# BLDC.net
KiCad netlist of a schematic drawn in EAGLE
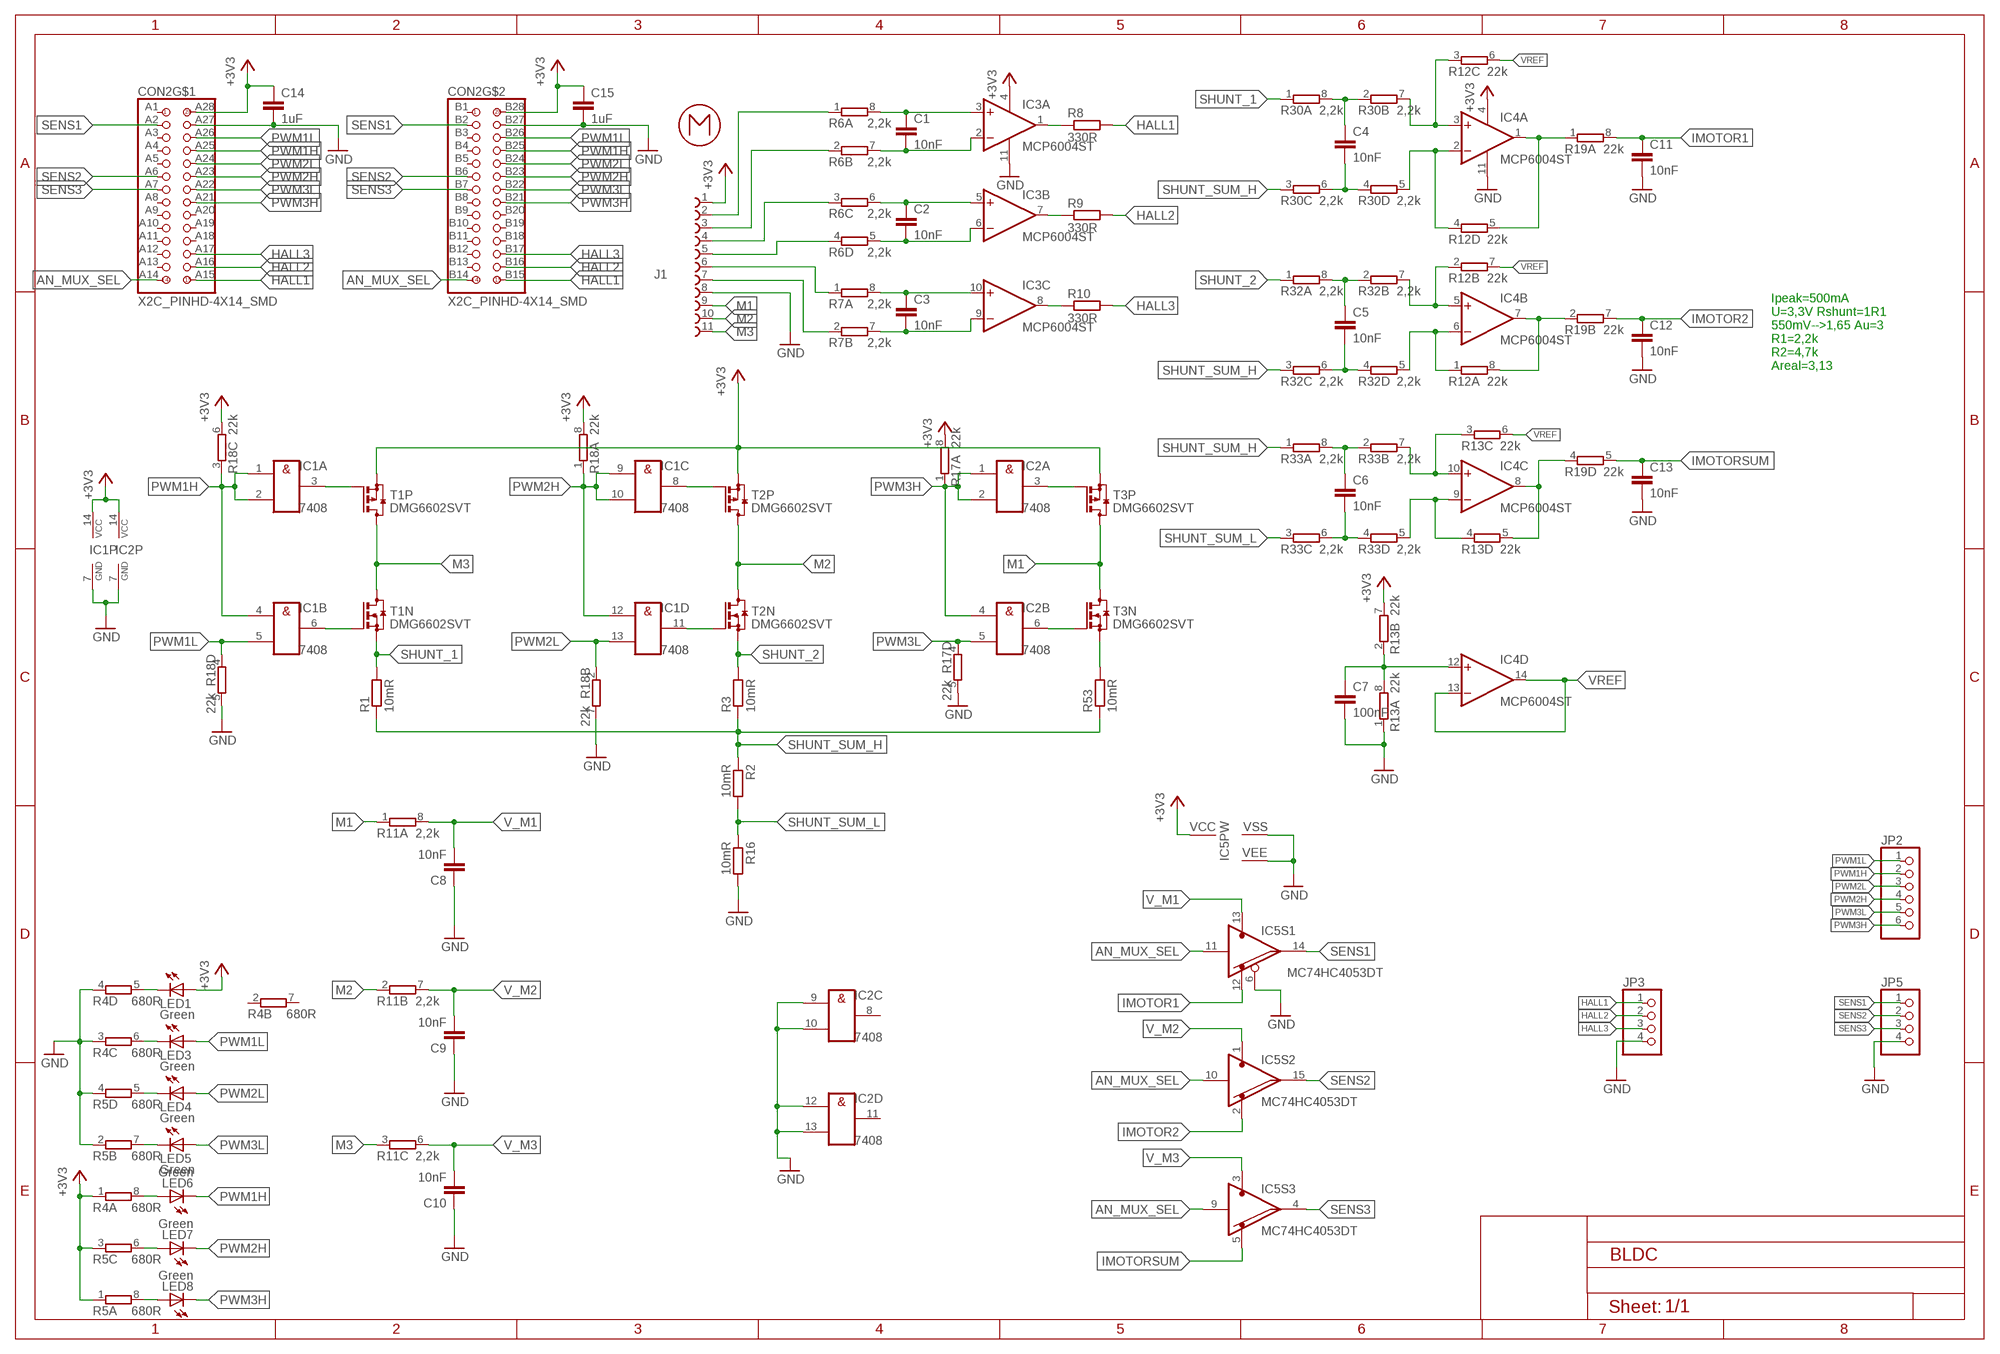
[diagram p0: schematic, sheet 1]

(export (version "E")
  (design (tool "Eeschema 10.0.6"))
  (components
    (comp (ref "C1")
      (value "10nF")
      (footprint "eagle-import:C0603K")
      (libsource (lib "eagle-import") (part "C-EU-SMD_0603_10NF"))
    )
    (comp (ref "C2")
      (value "10nF")
      (footprint "eagle-import:C0603K")
      (libsource (lib "eagle-import") (part "C-EU-SMD_0603_10NF"))
    )
    (comp (ref "C3")
      (value "10nF")
      (footprint "eagle-import:C0603K")
      (libsource (lib "eagle-import") (part "C-EU-SMD_0603_10NF"))
    )
    (comp (ref "C4")
      (value "10nF")
      (footprint "eagle-import:C0603K")
      (libsource (lib "eagle-import") (part "C-EU-SMD_0603_10NF"))
    )
    (comp (ref "C5")
      (value "10nF")
      (footprint "eagle-import:C0603K")
      (libsource (lib "eagle-import") (part "C-EU-SMD_0603_10NF"))
    )
    (comp (ref "C6")
      (value "10nF")
      (footprint "eagle-import:C0603K")
      (libsource (lib "eagle-import") (part "C-EU-SMD_0603_10NF"))
    )
    (comp (ref "C7")
      (value "100nF")
      (footprint "eagle-import:C0603K")
      (libsource (lib "eagle-import") (part "C-EU-SMD_0603_100NF_50V"))
    )
    (comp (ref "C8")
      (value "10nF")
      (footprint "eagle-import:C0603K")
      (libsource (lib "eagle-import") (part "C-EU-SMD_0603_10NF"))
    )
    (comp (ref "C9")
      (value "10nF")
      (footprint "eagle-import:C0603K")
      (libsource (lib "eagle-import") (part "C-EU-SMD_0603_10NF"))
    )
    (comp (ref "C10")
      (value "10nF")
      (footprint "eagle-import:C0603K")
      (libsource (lib "eagle-import") (part "C-EU-SMD_0603_10NF"))
    )
    (comp (ref "C11")
      (value "10nF")
      (footprint "eagle-import:C0603K")
      (libsource (lib "eagle-import") (part "C-EU-SMD_0603_10NF"))
    )
    (comp (ref "C12")
      (value "10nF")
      (footprint "eagle-import:C0603K")
      (libsource (lib "eagle-import") (part "C-EU-SMD_0603_10NF"))
    )
    (comp (ref "C13")
      (value "10nF")
      (footprint "eagle-import:C0603K")
      (libsource (lib "eagle-import") (part "C-EU-SMD_0603_10NF"))
    )
    (comp (ref "C14")
      (value "1uF")
      (footprint "eagle-import:C0603K")
      (libsource (lib "eagle-import") (part "C-EU-SMD_0603_1UF_10V"))
    )
    (comp (ref "C15")
      (value "1uF")
      (footprint "eagle-import:C0603K")
      (libsource (lib "eagle-import") (part "C-EU-SMD_0603_1UF_10V"))
    )
    (comp (ref "CON2")
      (value "X2C_PINHD-4X14_SMD")
      (footprint "eagle-import:X2C_4X14_SMD")
      (libsource (lib "eagle-import") (part "X2C_PINHD-4X14_SMD"))
    )
    (comp (ref "IC1")
      (value "7408")
      (footprint "eagle-import:TSSOP14")
      (libsource (lib "eagle-import") (part "7408"))
    )
    (comp (ref "IC2")
      (value "7408")
      (footprint "eagle-import:TSSOP14")
      (libsource (lib "eagle-import") (part "7408"))
    )
    (comp (ref "IC3")
      (value "MCP6004ST")
      (footprint "eagle-import:TSSOP14")
      (libsource (lib "eagle-import") (part "MCP6004ST"))
    )
    (comp (ref "IC4")
      (value "MCP6004ST")
      (footprint "eagle-import:TSSOP14")
      (libsource (lib "eagle-import") (part "MCP6004ST"))
    )
    (comp (ref "IC5")
      (value "MC74HC4053DT")
      (footprint "eagle-import:TSSOP16")
      (libsource (lib "eagle-import") (part "MC74HC4053DT"))
    )
    (comp (ref "J1")
      (value "68611114122")
      (footprint "eagle-import:68611114122")
      (libsource (lib "eagle-import") (part "68611114122"))
    )
    (comp (ref "JP2")
      (value "PINHD-1X6")
      (footprint "eagle-import:1X06")
      (libsource (lib "eagle-import") (part "PINHD-1X6"))
    )
    (comp (ref "JP3")
      (value "PINHD-1X4")
      (footprint "eagle-import:1X04")
      (libsource (lib "eagle-import") (part "PINHD-1X4"))
    )
    (comp (ref "JP5")
      (value "PINHD-1X4")
      (footprint "eagle-import:1X04")
      (libsource (lib "eagle-import") (part "PINHD-1X4"))
    )
    (comp (ref "LED1")
      (value "Green")
      (footprint "eagle-import:CHIPLED_0805")
      (libsource (lib "eagle-import") (part "LEDCHIPLED_0805_GREEN"))
    )
    (comp (ref "LED3")
      (value "Green")
      (footprint "eagle-import:CHIPLED_0805")
      (libsource (lib "eagle-import") (part "LEDCHIPLED_0805_GREEN"))
    )
    (comp (ref "LED4")
      (value "Green")
      (footprint "eagle-import:CHIPLED_0805")
      (libsource (lib "eagle-import") (part "LEDCHIPLED_0805_GREEN"))
    )
    (comp (ref "LED5")
      (value "Green")
      (footprint "eagle-import:CHIPLED_0805")
      (libsource (lib "eagle-import") (part "LEDCHIPLED_0805_GREEN"))
    )
    (comp (ref "LED6")
      (value "Green")
      (footprint "eagle-import:CHIPLED_0805")
      (libsource (lib "eagle-import") (part "LEDCHIPLED_0805_GREEN"))
    )
    (comp (ref "LED7")
      (value "Green")
      (footprint "eagle-import:CHIPLED_0805")
      (libsource (lib "eagle-import") (part "LEDCHIPLED_0805_GREEN"))
    )
    (comp (ref "LED8")
      (value "Green")
      (footprint "eagle-import:CHIPLED_0805")
      (libsource (lib "eagle-import") (part "LEDCHIPLED_0805_GREEN"))
    )
    (comp (ref "R1")
      (value "10mR")
      (footprint "eagle-import:R1206")
      (libsource (lib "eagle-import") (part "R-EU_SMDR1206_0,01R"))
    )
    (comp (ref "R2")
      (value "10mR")
      (footprint "eagle-import:R1206")
      (libsource (lib "eagle-import") (part "R-EU_SMDR1206_0,01R"))
    )
    (comp (ref "R3")
      (value "10mR")
      (footprint "eagle-import:R1206")
      (libsource (lib "eagle-import") (part "R-EU_SMDR1206_0,01R"))
    )
    (comp (ref "R4")
      (value "680R")
      (footprint "eagle-import:EXBV8V_A")
      (libsource (lib "eagle-import") (part "4R-N680R"))
    )
    (comp (ref "R5")
      (value "680R")
      (footprint "eagle-import:EXBV8V_A")
      (libsource (lib "eagle-import") (part "4R-N680R"))
    )
    (comp (ref "R6")
      (value "2,2k")
      (footprint "eagle-import:EXBV8V_A")
      (libsource (lib "eagle-import") (part "4R-N2,2K"))
    )
    (comp (ref "R7")
      (value "2,2k")
      (footprint "eagle-import:EXBV8V_A")
      (libsource (lib "eagle-import") (part "4R-N2,2K"))
    )
    (comp (ref "R8")
      (value "330R")
      (footprint "eagle-import:R0603")
      (libsource (lib "eagle-import") (part "R-EU_SMDR0603_330R"))
    )
    (comp (ref "R9")
      (value "330R")
      (footprint "eagle-import:R0603")
      (libsource (lib "eagle-import") (part "R-EU_SMDR0603_330R"))
    )
    (comp (ref "R10")
      (value "330R")
      (footprint "eagle-import:R0603")
      (libsource (lib "eagle-import") (part "R-EU_SMDR0603_330R"))
    )
    (comp (ref "R11")
      (value "2,2k")
      (footprint "eagle-import:EXBV8V_A")
      (libsource (lib "eagle-import") (part "4R-N2,2K"))
    )
    (comp (ref "R12")
      (value "22k")
      (footprint "eagle-import:EXBV8V_A")
      (libsource (lib "eagle-import") (part "4R-N22K"))
    )
    (comp (ref "R13")
      (value "22k")
      (footprint "eagle-import:EXBV8V_A")
      (libsource (lib "eagle-import") (part "4R-N22K"))
    )
    (comp (ref "R16")
      (value "10mR")
      (footprint "eagle-import:R1206")
      (libsource (lib "eagle-import") (part "R-EU_SMDR1206_0,01R"))
    )
    (comp (ref "R17")
      (value "22k")
      (footprint "eagle-import:EXBV8V_A")
      (libsource (lib "eagle-import") (part "4R-N22K"))
    )
    (comp (ref "R18")
      (value "22k")
      (footprint "eagle-import:EXBV8V_A")
      (libsource (lib "eagle-import") (part "4R-N22K"))
    )
    (comp (ref "R19")
      (value "22k")
      (footprint "eagle-import:EXBV8V_A")
      (libsource (lib "eagle-import") (part "4R-N22K"))
    )
    (comp (ref "R30")
      (value "2,2k")
      (footprint "eagle-import:EXBV8V_A")
      (libsource (lib "eagle-import") (part "4R-N2,2K"))
    )
    (comp (ref "R32")
      (value "2,2k")
      (footprint "eagle-import:EXBV8V_A")
      (libsource (lib "eagle-import") (part "4R-N2,2K"))
    )
    (comp (ref "R33")
      (value "2,2k")
      (footprint "eagle-import:EXBV8V_A")
      (libsource (lib "eagle-import") (part "4R-N2,2K"))
    )
    (comp (ref "R53")
      (value "10mR")
      (footprint "eagle-import:R1206")
      (libsource (lib "eagle-import") (part "R-EU_SMDR1206_0,01R"))
    )
    (comp (ref "T1")
      (value "DMG6602SVT")
      (footprint "eagle-import:TSOT23-6")
      (libsource (lib "eagle-import") (part "DMG6602SVT"))
    )
    (comp (ref "T2")
      (value "DMG6602SVT")
      (footprint "eagle-import:TSOT23-6")
      (libsource (lib "eagle-import") (part "DMG6602SVT"))
    )
    (comp (ref "T3")
      (value "DMG6602SVT")
      (footprint "eagle-import:TSOT23-6")
      (libsource (lib "eagle-import") (part "DMG6602SVT"))
    )
    (comp (ref "U$2")
      (value "BLDC_MOTOR")
      (footprint "eagle-import:BLDC_MOTOR")
      (libsource (lib "eagle-import") (part "BLDC_MOTOR"))
    )
  )
  (nets
    (net (code "1") (name "+3V3") (class "Default")
      (node (ref "C14") (pin "1") (pinfunction "1_1") (pintype "passive"))
      (node (ref "C15") (pin "1") (pinfunction "1_1") (pintype "passive"))
      (node (ref "CON2") (pin "A28") (pinfunction "A28_A28") (pintype "passive"))
      (node (ref "CON2") (pin "B28") (pinfunction "A28_B28") (pintype "passive"))
      (node (ref "IC1") (pin "14") (pinfunction "VCC_14") (pintype "power_in"))
      (node (ref "IC2") (pin "14") (pinfunction "VCC_14") (pintype "power_in"))
      (node (ref "IC3") (pin "4") (pinfunction "V+_4") (pintype "power_in"))
      (node (ref "IC4") (pin "4") (pinfunction "V+_4") (pintype "power_in"))
      (node (ref "IC5") (pin "16") (pinfunction "VCC_16") (pintype "power_in"))
      (node (ref "J1") (pin "1") (pinfunction "1_1") (pintype "passive"))
      (node (ref "LED1") (pin "A") (pinfunction "A_A") (pintype "passive"))
      (node (ref "R13") (pin "7") (pinfunction "2_7") (pintype "passive"))
      (node (ref "R17") (pin "8") (pinfunction "2_8") (pintype "passive"))
      (node (ref "R18") (pin "6") (pinfunction "2_6") (pintype "passive"))
      (node (ref "R18") (pin "8") (pinfunction "2_8") (pintype "passive"))
      (node (ref "R4") (pin "1") (pinfunction "1_1") (pintype "passive"))
      (node (ref "R5") (pin "1") (pinfunction "1_1") (pintype "passive"))
      (node (ref "R5") (pin "3") (pinfunction "1_3") (pintype "passive"))
      (node (ref "T1") (pin "2") (pinfunction "S_2") (pintype "passive"))
      (node (ref "T2") (pin "2") (pinfunction "S_2") (pintype "passive"))
      (node (ref "T3") (pin "2") (pinfunction "S_2") (pintype "passive"))
    )
    (net (code "2") (name "AN_MUX_SEL") (class "Default")
      (node (ref "CON2") (pin "A14") (pinfunction "A14_A14") (pintype "passive"))
      (node (ref "CON2") (pin "B14") (pinfunction "A14_B14") (pintype "passive"))
      (node (ref "IC5") (pin "10") (pinfunction "I_10") (pintype "input"))
      (node (ref "IC5") (pin "11") (pinfunction "I_11") (pintype "input"))
      (node (ref "IC5") (pin "9") (pinfunction "I_9") (pintype "input"))
    )
    (net (code "3") (name "GND") (class "Default")
      (node (ref "C10") (pin "1") (pinfunction "1_1") (pintype "passive"))
      (node (ref "C11") (pin "2") (pinfunction "2_2") (pintype "passive"))
      (node (ref "C12") (pin "2") (pinfunction "2_2") (pintype "passive"))
      (node (ref "C13") (pin "2") (pinfunction "2_2") (pintype "passive"))
      (node (ref "C14") (pin "2") (pinfunction "2_2") (pintype "passive"))
      (node (ref "C15") (pin "2") (pinfunction "2_2") (pintype "passive"))
      (node (ref "C7") (pin "2") (pinfunction "2_2") (pintype "passive"))
      (node (ref "C8") (pin "1") (pinfunction "1_1") (pintype "passive"))
      (node (ref "C9") (pin "1") (pinfunction "1_1") (pintype "passive"))
      (node (ref "CON2") (pin "A27") (pinfunction "A27_A27") (pintype "passive"))
      (node (ref "CON2") (pin "B27") (pinfunction "A27_B27") (pintype "passive"))
      (node (ref "IC1") (pin "7") (pinfunction "GND_7") (pintype "power_in"))
      (node (ref "IC2") (pin "10") (pinfunction "I1_10") (pintype "input"))
      (node (ref "IC2") (pin "12") (pinfunction "I0_12") (pintype "input"))
      (node (ref "IC2") (pin "13") (pinfunction "I1_13") (pintype "input"))
      (node (ref "IC2") (pin "7") (pinfunction "GND_7") (pintype "power_in"))
      (node (ref "IC2") (pin "9") (pinfunction "I0_9") (pintype "input"))
      (node (ref "IC3") (pin "11") (pinfunction "V-_11") (pintype "power_in"))
      (node (ref "IC4") (pin "11") (pinfunction "V-_11") (pintype "power_in"))
      (node (ref "IC5") (pin "6") (pinfunction "P$1_6") (pintype "input"))
      (node (ref "IC5") (pin "7") (pinfunction "VEE_7") (pintype "power_in"))
      (node (ref "IC5") (pin "8") (pinfunction "GND_8") (pintype "power_in"))
      (node (ref "J1") (pin "8") (pinfunction "8_8") (pintype "passive"))
      (node (ref "JP3") (pin "4") (pinfunction "4_4") (pintype "passive"))
      (node (ref "JP5") (pin "4") (pinfunction "4_4") (pintype "passive"))
      (node (ref "R13") (pin "1") (pinfunction "1_1") (pintype "passive"))
      (node (ref "R16") (pin "2") (pinfunction "2_2") (pintype "passive"))
      (node (ref "R17") (pin "5") (pinfunction "2_5") (pintype "passive"))
      (node (ref "R18") (pin "5") (pinfunction "2_5") (pintype "passive"))
      (node (ref "R18") (pin "7") (pinfunction "2_7") (pintype "passive"))
      (node (ref "R4") (pin "3") (pinfunction "1_3") (pintype "passive"))
      (node (ref "R4") (pin "4") (pinfunction "1_4") (pintype "passive"))
      (node (ref "R5") (pin "2") (pinfunction "1_2") (pintype "passive"))
      (node (ref "R5") (pin "4") (pinfunction "1_4") (pintype "passive"))
    )
    (net (code "4") (name "HALL1") (class "Default")
      (node (ref "CON2") (pin "A15") (pinfunction "A15_A15") (pintype "passive"))
      (node (ref "CON2") (pin "B15") (pinfunction "A15_B15") (pintype "passive"))
      (node (ref "JP3") (pin "1") (pinfunction "1_1") (pintype "passive"))
      (node (ref "R8") (pin "2") (pinfunction "2_2") (pintype "passive"))
    )
    (net (code "5") (name "HALL2") (class "Default")
      (node (ref "CON2") (pin "A16") (pinfunction "A16_A16") (pintype "passive"))
      (node (ref "CON2") (pin "B16") (pinfunction "A16_B16") (pintype "passive"))
      (node (ref "JP3") (pin "2") (pinfunction "2_2") (pintype "passive"))
      (node (ref "R9") (pin "2") (pinfunction "2_2") (pintype "passive"))
    )
    (net (code "6") (name "HALL3") (class "Default")
      (node (ref "CON2") (pin "A17") (pinfunction "A17_A17") (pintype "passive"))
      (node (ref "CON2") (pin "B17") (pinfunction "A17_B17") (pintype "passive"))
      (node (ref "JP3") (pin "3") (pinfunction "3_3") (pintype "passive"))
      (node (ref "R10") (pin "2") (pinfunction "2_2") (pintype "passive"))
    )
    (net (code "7") (name "IMOTOR1") (class "Default")
      (node (ref "C11") (pin "1") (pinfunction "1_1") (pintype "passive"))
      (node (ref "IC5") (pin "12") (pinfunction "O2_12") (pintype "bidirectional"))
      (node (ref "R19") (pin "8") (pinfunction "2_8") (pintype "passive"))
    )
    (net (code "8") (name "IMOTOR2") (class "Default")
      (node (ref "C12") (pin "1") (pinfunction "1_1") (pintype "passive"))
      (node (ref "IC5") (pin "2") (pinfunction "O2_2") (pintype "bidirectional"))
      (node (ref "R19") (pin "7") (pinfunction "2_7") (pintype "passive"))
    )
    (net (code "9") (name "IMOTORSUM") (class "Default")
      (node (ref "C13") (pin "1") (pinfunction "1_1") (pintype "passive"))
      (node (ref "IC5") (pin "5") (pinfunction "O2_5") (pintype "bidirectional"))
      (node (ref "R19") (pin "5") (pinfunction "2_5") (pintype "passive"))
    )
    (net (code "10") (name "M1") (class "Default")
      (node (ref "J1") (pin "9") (pinfunction "9_9") (pintype "passive"))
      (node (ref "R11") (pin "1") (pinfunction "1_1") (pintype "passive"))
      (node (ref "T3") (pin "4") (pinfunction "D_4") (pintype "passive"))
      (node (ref "T3") (pin "6") (pinfunction "D_6") (pintype "passive"))
    )
    (net (code "11") (name "M2") (class "Default")
      (node (ref "J1") (pin "10") (pinfunction "10_10") (pintype "passive"))
      (node (ref "R11") (pin "2") (pinfunction "1_2") (pintype "passive"))
      (node (ref "T2") (pin "4") (pinfunction "D_4") (pintype "passive"))
      (node (ref "T2") (pin "6") (pinfunction "D_6") (pintype "passive"))
    )
    (net (code "12") (name "M3") (class "Default")
      (node (ref "J1") (pin "11") (pinfunction "11_11") (pintype "passive"))
      (node (ref "R11") (pin "3") (pinfunction "1_3") (pintype "passive"))
      (node (ref "T1") (pin "4") (pinfunction "D_4") (pintype "passive"))
      (node (ref "T1") (pin "6") (pinfunction "D_6") (pintype "passive"))
    )
    (net (code "13") (name "Net-(IC1A-O)") (class "Default")
      (node (ref "IC1") (pin "3") (pinfunction "O_3") (pintype "output"))
      (node (ref "T1") (pin "3") (pinfunction "G_3") (pintype "passive"))
    )
    (net (code "14") (name "Net-(IC1B-O)") (class "Default")
      (node (ref "IC1") (pin "6") (pinfunction "O_6") (pintype "output"))
      (node (ref "T1") (pin "1") (pinfunction "G_1") (pintype "passive"))
    )
    (net (code "15") (name "Net-(IC1C-O)") (class "Default")
      (node (ref "IC1") (pin "8") (pinfunction "O_8") (pintype "output"))
      (node (ref "T2") (pin "3") (pinfunction "G_3") (pintype "passive"))
    )
    (net (code "16") (name "Net-(IC1D-O)") (class "Default")
      (node (ref "IC1") (pin "11") (pinfunction "O_11") (pintype "output"))
      (node (ref "T2") (pin "1") (pinfunction "G_1") (pintype "passive"))
    )
    (net (code "17") (name "Net-(IC2A-O)") (class "Default")
      (node (ref "IC2") (pin "3") (pinfunction "O_3") (pintype "output"))
      (node (ref "T3") (pin "3") (pinfunction "G_3") (pintype "passive"))
    )
    (net (code "18") (name "Net-(IC2B-O)") (class "Default")
      (node (ref "IC2") (pin "6") (pinfunction "O_6") (pintype "output"))
      (node (ref "T3") (pin "1") (pinfunction "G_1") (pintype "passive"))
    )
    (net (code "19") (name "Net-(IC3A-+IN)") (class "Default")
      (node (ref "C1") (pin "1") (pinfunction "1_1") (pintype "passive"))
      (node (ref "IC3") (pin "3") (pinfunction "+IN_3") (pintype "input"))
      (node (ref "R6") (pin "8") (pinfunction "2_8") (pintype "passive"))
    )
    (net (code "20") (name "Net-(IC3A--IN)") (class "Default")
      (node (ref "C1") (pin "2") (pinfunction "2_2") (pintype "passive"))
      (node (ref "IC3") (pin "2") (pinfunction "-IN_2") (pintype "input"))
      (node (ref "R6") (pin "7") (pinfunction "2_7") (pintype "passive"))
    )
    (net (code "21") (name "Net-(IC3A-OUT)") (class "Default")
      (node (ref "IC3") (pin "1") (pinfunction "OUT_1") (pintype "output"))
      (node (ref "R8") (pin "1") (pinfunction "1_1") (pintype "passive"))
    )
    (net (code "22") (name "Net-(IC3B-+IN)") (class "Default")
      (node (ref "C2") (pin "1") (pinfunction "1_1") (pintype "passive"))
      (node (ref "IC3") (pin "5") (pinfunction "+IN_5") (pintype "input"))
      (node (ref "R6") (pin "6") (pinfunction "2_6") (pintype "passive"))
    )
    (net (code "23") (name "Net-(IC3B--IN)") (class "Default")
      (node (ref "C2") (pin "2") (pinfunction "2_2") (pintype "passive"))
      (node (ref "IC3") (pin "6") (pinfunction "-IN_6") (pintype "input"))
      (node (ref "R6") (pin "5") (pinfunction "2_5") (pintype "passive"))
    )
    (net (code "24") (name "Net-(IC3B-OUT)") (class "Default")
      (node (ref "IC3") (pin "7") (pinfunction "OUT_7") (pintype "output"))
      (node (ref "R9") (pin "1") (pinfunction "1_1") (pintype "passive"))
    )
    (net (code "25") (name "Net-(IC3C-+IN)") (class "Default")
      (node (ref "C3") (pin "1") (pinfunction "1_1") (pintype "passive"))
      (node (ref "IC3") (pin "10") (pinfunction "+IN_10") (pintype "input"))
      (node (ref "R7") (pin "8") (pinfunction "2_8") (pintype "passive"))
    )
    (net (code "26") (name "Net-(IC3C--IN)") (class "Default")
      (node (ref "C3") (pin "2") (pinfunction "2_2") (pintype "passive"))
      (node (ref "IC3") (pin "9") (pinfunction "-IN_9") (pintype "input"))
      (node (ref "R7") (pin "7") (pinfunction "2_7") (pintype "passive"))
    )
    (net (code "27") (name "Net-(IC3C-OUT)") (class "Default")
      (node (ref "IC3") (pin "8") (pinfunction "OUT_8") (pintype "output"))
      (node (ref "R10") (pin "1") (pinfunction "1_1") (pintype "passive"))
    )
    (net (code "28") (name "Net-(IC4A-+IN)") (class "Default")
      (node (ref "IC4") (pin "3") (pinfunction "+IN_3") (pintype "input"))
      (node (ref "R12") (pin "3") (pinfunction "1_3") (pintype "passive"))
      (node (ref "R30") (pin "7") (pinfunction "2_7") (pintype "passive"))
    )
    (net (code "29") (name "Net-(IC4A--IN)") (class "Default")
      (node (ref "IC4") (pin "2") (pinfunction "-IN_2") (pintype "input"))
      (node (ref "R12") (pin "4") (pinfunction "1_4") (pintype "passive"))
      (node (ref "R30") (pin "5") (pinfunction "2_5") (pintype "passive"))
    )
    (net (code "30") (name "Net-(IC4A-OUT)") (class "Default")
      (node (ref "IC4") (pin "1") (pinfunction "OUT_1") (pintype "output"))
      (node (ref "R12") (pin "5") (pinfunction "2_5") (pintype "passive"))
      (node (ref "R19") (pin "1") (pinfunction "1_1") (pintype "passive"))
    )
    (net (code "31") (name "Net-(IC4B-+IN)") (class "Default")
      (node (ref "IC4") (pin "5") (pinfunction "+IN_5") (pintype "input"))
      (node (ref "R12") (pin "2") (pinfunction "1_2") (pintype "passive"))
      (node (ref "R32") (pin "7") (pinfunction "2_7") (pintype "passive"))
    )
    (net (code "32") (name "Net-(IC4B--IN)") (class "Default")
      (node (ref "IC4") (pin "6") (pinfunction "-IN_6") (pintype "input"))
      (node (ref "R12") (pin "1") (pinfunction "1_1") (pintype "passive"))
      (node (ref "R32") (pin "5") (pinfunction "2_5") (pintype "passive"))
    )
    (net (code "33") (name "Net-(IC4B-OUT)") (class "Default")
      (node (ref "IC4") (pin "7") (pinfunction "OUT_7") (pintype "output"))
      (node (ref "R12") (pin "8") (pinfunction "2_8") (pintype "passive"))
      (node (ref "R19") (pin "2") (pinfunction "1_2") (pintype "passive"))
    )
    (net (code "34") (name "Net-(IC4C-+IN)") (class "Default")
      (node (ref "IC4") (pin "10") (pinfunction "+IN_10") (pintype "input"))
      (node (ref "R13") (pin "3") (pinfunction "1_3") (pintype "passive"))
      (node (ref "R33") (pin "7") (pinfunction "2_7") (pintype "passive"))
    )
    (net (code "35") (name "Net-(IC4C--IN)") (class "Default")
      (node (ref "IC4") (pin "9") (pinfunction "-IN_9") (pintype "input"))
      (node (ref "R13") (pin "4") (pinfunction "1_4") (pintype "passive"))
      (node (ref "R33") (pin "5") (pinfunction "2_5") (pintype "passive"))
    )
    (net (code "36") (name "Net-(IC4C-OUT)") (class "Default")
      (node (ref "IC4") (pin "8") (pinfunction "OUT_8") (pintype "output"))
      (node (ref "R13") (pin "5") (pinfunction "2_5") (pintype "passive"))
      (node (ref "R19") (pin "4") (pinfunction "1_4") (pintype "passive"))
    )
    (net (code "37") (name "Net-(IC4D-+IN)") (class "Default")
      (node (ref "C7") (pin "1") (pinfunction "1_1") (pintype "passive"))
      (node (ref "IC4") (pin "12") (pinfunction "+IN_12") (pintype "input"))
      (node (ref "R13") (pin "2") (pinfunction "1_2") (pintype "passive"))
      (node (ref "R13") (pin "8") (pinfunction "2_8") (pintype "passive"))
    )
    (net (code "38") (name "Net-(J1-Pad2)") (class "Default")
      (node (ref "J1") (pin "2") (pinfunction "2_2") (pintype "passive"))
      (node (ref "R6") (pin "1") (pinfunction "1_1") (pintype "passive"))
    )
    (net (code "39") (name "Net-(J1-Pad6)") (class "Default")
      (node (ref "J1") (pin "6") (pinfunction "6_6") (pintype "passive"))
      (node (ref "R7") (pin "1") (pinfunction "1_1") (pintype "passive"))
    )
    (net (code "40") (name "Net-(R4A-2)") (class "Default")
      (node (ref "LED6") (pin "A") (pinfunction "A_A") (pintype "passive"))
      (node (ref "R4") (pin "8") (pinfunction "2_8") (pintype "passive"))
    )
    (net (code "41") (name "Net-(R4C-2)") (class "Default")
      (node (ref "LED3") (pin "C") (pinfunction "C_C") (pintype "passive"))
      (node (ref "R4") (pin "6") (pinfunction "2_6") (pintype "passive"))
    )
    (net (code "42") (name "Net-(R4D-2)") (class "Default")
      (node (ref "LED1") (pin "C") (pinfunction "C_C") (pintype "passive"))
      (node (ref "R4") (pin "5") (pinfunction "2_5") (pintype "passive"))
    )
    (net (code "43") (name "Net-(R5A-2)") (class "Default")
      (node (ref "LED8") (pin "A") (pinfunction "A_A") (pintype "passive"))
      (node (ref "R5") (pin "8") (pinfunction "2_8") (pintype "passive"))
    )
    (net (code "44") (name "Net-(R5B-2)") (class "Default")
      (node (ref "LED5") (pin "C") (pinfunction "C_C") (pintype "passive"))
      (node (ref "R5") (pin "7") (pinfunction "2_7") (pintype "passive"))
    )
    (net (code "45") (name "Net-(R5C-2)") (class "Default")
      (node (ref "LED7") (pin "A") (pinfunction "A_A") (pintype "passive"))
      (node (ref "R5") (pin "6") (pinfunction "2_6") (pintype "passive"))
    )
    (net (code "46") (name "Net-(R5D-2)") (class "Default")
      (node (ref "LED4") (pin "C") (pinfunction "C_C") (pintype "passive"))
      (node (ref "R5") (pin "5") (pinfunction "2_5") (pintype "passive"))
    )
    (net (code "47") (name "Net-(R6B-1)") (class "Default")
      (node (ref "J1") (pin "3") (pinfunction "3_3") (pintype "passive"))
      (node (ref "R6") (pin "2") (pinfunction "1_2") (pintype "passive"))
    )
    (net (code "48") (name "Net-(R6C-1)") (class "Default")
      (node (ref "J1") (pin "4") (pinfunction "4_4") (pintype "passive"))
      (node (ref "R6") (pin "3") (pinfunction "1_3") (pintype "passive"))
    )
    (net (code "49") (name "Net-(R6D-1)") (class "Default")
      (node (ref "J1") (pin "5") (pinfunction "5_5") (pintype "passive"))
      (node (ref "R6") (pin "4") (pinfunction "1_4") (pintype "passive"))
    )
    (net (code "50") (name "Net-(R7B-1)") (class "Default")
      (node (ref "J1") (pin "7") (pinfunction "7_7") (pintype "passive"))
      (node (ref "R7") (pin "2") (pinfunction "1_2") (pintype "passive"))
    )
    (net (code "51") (name "Net-(R30A-2)") (class "Default")
      (node (ref "C4") (pin "1") (pinfunction "1_1") (pintype "passive"))
      (node (ref "R30") (pin "2") (pinfunction "1_2") (pintype "passive"))
      (node (ref "R30") (pin "8") (pinfunction "2_8") (pintype "passive"))
    )
    (net (code "52") (name "Net-(R30C-2)") (class "Default")
      (node (ref "C4") (pin "2") (pinfunction "2_2") (pintype "passive"))
      (node (ref "R30") (pin "4") (pinfunction "1_4") (pintype "passive"))
      (node (ref "R30") (pin "6") (pinfunction "2_6") (pintype "passive"))
    )
    (net (code "53") (name "Net-(R32A-2)") (class "Default")
      (node (ref "C5") (pin "1") (pinfunction "1_1") (pintype "passive"))
      (node (ref "R32") (pin "2") (pinfunction "1_2") (pintype "passive"))
      (node (ref "R32") (pin "8") (pinfunction "2_8") (pintype "passive"))
    )
    (net (code "54") (name "Net-(R32C-2)") (class "Default")
      (node (ref "C5") (pin "2") (pinfunction "2_2") (pintype "passive"))
      (node (ref "R32") (pin "4") (pinfunction "1_4") (pintype "passive"))
      (node (ref "R32") (pin "6") (pinfunction "2_6") (pintype "passive"))
    )
    (net (code "55") (name "Net-(R33A-2)") (class "Default")
      (node (ref "C6") (pin "1") (pinfunction "1_1") (pintype "passive"))
      (node (ref "R33") (pin "2") (pinfunction "1_2") (pintype "passive"))
      (node (ref "R33") (pin "8") (pinfunction "2_8") (pintype "passive"))
    )
    (net (code "56") (name "Net-(R33C-2)") (class "Default")
      (node (ref "C6") (pin "2") (pinfunction "2_2") (pintype "passive"))
      (node (ref "R33") (pin "4") (pinfunction "1_4") (pintype "passive"))
      (node (ref "R33") (pin "6") (pinfunction "2_6") (pintype "passive"))
    )
    (net (code "57") (name "Net-(T3A-S)") (class "Default")
      (node (ref "R53") (pin "2") (pinfunction "2_2") (pintype "passive"))
      (node (ref "T3") (pin "5") (pinfunction "S_5") (pintype "passive"))
    )
    (net (code "58") (name "PWM1H") (class "Default")
      (node (ref "CON2") (pin "A25") (pinfunction "A25_A25") (pintype "passive"))
      (node (ref "CON2") (pin "B25") (pinfunction "A25_B25") (pintype "passive"))
      (node (ref "IC1") (pin "1") (pinfunction "I0_1") (pintype "input"))
      (node (ref "IC1") (pin "2") (pinfunction "I1_2") (pintype "input"))
      (node (ref "IC1") (pin "4") (pinfunction "I0_4") (pintype "input"))
      (node (ref "JP2") (pin "2") (pinfunction "2_2") (pintype "passive"))
      (node (ref "LED6") (pin "C") (pinfunction "C_C") (pintype "passive"))
      (node (ref "R18") (pin "3") (pinfunction "1_3") (pintype "passive"))
    )
    (net (code "59") (name "PWM1L") (class "Default")
      (node (ref "CON2") (pin "A26") (pinfunction "A26_A26") (pintype "passive"))
      (node (ref "CON2") (pin "B26") (pinfunction "A26_B26") (pintype "passive"))
      (node (ref "IC1") (pin "5") (pinfunction "I1_5") (pintype "input"))
      (node (ref "JP2") (pin "1") (pinfunction "1_1") (pintype "passive"))
      (node (ref "LED3") (pin "A") (pinfunction "A_A") (pintype "passive"))
      (node (ref "R18") (pin "4") (pinfunction "1_4") (pintype "passive"))
    )
    (net (code "60") (name "PWM2H") (class "Default")
      (node (ref "CON2") (pin "A23") (pinfunction "A23_A23") (pintype "passive"))
      (node (ref "CON2") (pin "B23") (pinfunction "A23_B23") (pintype "passive"))
      (node (ref "IC1") (pin "10") (pinfunction "I1_10") (pintype "input"))
      (node (ref "IC1") (pin "12") (pinfunction "I0_12") (pintype "input"))
      (node (ref "IC1") (pin "9") (pinfunction "I0_9") (pintype "input"))
      (node (ref "JP2") (pin "4") (pinfunction "4_4") (pintype "passive"))
      (node (ref "LED7") (pin "C") (pinfunction "C_C") (pintype "passive"))
      (node (ref "R18") (pin "1") (pinfunction "1_1") (pintype "passive"))
    )
    (net (code "61") (name "PWM2L") (class "Default")
      (node (ref "CON2") (pin "A24") (pinfunction "A24_A24") (pintype "passive"))
      (node (ref "CON2") (pin "B24") (pinfunction "A24_B24") (pintype "passive"))
      (node (ref "IC1") (pin "13") (pinfunction "I1_13") (pintype "input"))
      (node (ref "JP2") (pin "3") (pinfunction "3_3") (pintype "passive"))
      (node (ref "LED4") (pin "A") (pinfunction "A_A") (pintype "passive"))
      (node (ref "R18") (pin "2") (pinfunction "1_2") (pintype "passive"))
    )
    (net (code "62") (name "PWM3H") (class "Default")
      (node (ref "CON2") (pin "A21") (pinfunction "A21_A21") (pintype "passive"))
      (node (ref "CON2") (pin "B21") (pinfunction "A21_B21") (pintype "passive"))
      (node (ref "IC2") (pin "1") (pinfunction "I0_1") (pintype "input"))
      (node (ref "IC2") (pin "2") (pinfunction "I1_2") (pintype "input"))
      (node (ref "IC2") (pin "4") (pinfunction "I0_4") (pintype "input"))
      (node (ref "JP2") (pin "6") (pinfunction "6_6") (pintype "passive"))
      (node (ref "LED8") (pin "C") (pinfunction "C_C") (pintype "passive"))
      (node (ref "R17") (pin "1") (pinfunction "1_1") (pintype "passive"))
    )
    (net (code "63") (name "PWM3L") (class "Default")
      (node (ref "CON2") (pin "A22") (pinfunction "A22_A22") (pintype "passive"))
      (node (ref "CON2") (pin "B22") (pinfunction "A22_B22") (pintype "passive"))
      (node (ref "IC2") (pin "5") (pinfunction "I1_5") (pintype "input"))
      (node (ref "JP2") (pin "5") (pinfunction "5_5") (pintype "passive"))
      (node (ref "LED5") (pin "A") (pinfunction "A_A") (pintype "passive"))
      (node (ref "R17") (pin "4") (pinfunction "1_4") (pintype "passive"))
    )
    (net (code "64") (name "SENS1") (class "Default")
      (node (ref "CON2") (pin "A2") (pinfunction "A2_A2") (pintype "passive"))
      (node (ref "CON2") (pin "B2") (pinfunction "A2_B2") (pintype "passive"))
      (node (ref "IC5") (pin "14") (pinfunction "O_14") (pintype "bidirectional"))
      (node (ref "JP5") (pin "1") (pinfunction "1_1") (pintype "passive"))
    )
    (net (code "65") (name "SENS2") (class "Default")
      (node (ref "CON2") (pin "A6") (pinfunction "A6_A6") (pintype "passive"))
      (node (ref "CON2") (pin "B6") (pinfunction "A6_B6") (pintype "passive"))
      (node (ref "IC5") (pin "15") (pinfunction "O_15") (pintype "bidirectional"))
      (node (ref "JP5") (pin "2") (pinfunction "2_2") (pintype "passive"))
    )
    (net (code "66") (name "SENS3") (class "Default")
      (node (ref "CON2") (pin "A7") (pinfunction "A7_A7") (pintype "passive"))
      (node (ref "CON2") (pin "B7") (pinfunction "A7_B7") (pintype "passive"))
      (node (ref "IC5") (pin "4") (pinfunction "O_4") (pintype "bidirectional"))
      (node (ref "JP5") (pin "3") (pinfunction "3_3") (pintype "passive"))
    )
    (net (code "67") (name "SHUNT_1") (class "Default")
      (node (ref "R1") (pin "2") (pinfunction "2_2") (pintype "passive"))
      (node (ref "R30") (pin "1") (pinfunction "1_1") (pintype "passive"))
      (node (ref "T1") (pin "5") (pinfunction "S_5") (pintype "passive"))
    )
    (net (code "68") (name "SHUNT_2") (class "Default")
      (node (ref "R3") (pin "2") (pinfunction "2_2") (pintype "passive"))
      (node (ref "R32") (pin "1") (pinfunction "1_1") (pintype "passive"))
      (node (ref "T2") (pin "5") (pinfunction "S_5") (pintype "passive"))
    )
    (net (code "69") (name "SHUNT_SUM_H") (class "Default")
      (node (ref "R1") (pin "1") (pinfunction "1_1") (pintype "passive"))
      (node (ref "R2") (pin "1") (pinfunction "1_1") (pintype "passive"))
      (node (ref "R3") (pin "1") (pinfunction "1_1") (pintype "passive"))
      (node (ref "R30") (pin "3") (pinfunction "1_3") (pintype "passive"))
      (node (ref "R32") (pin "3") (pinfunction "1_3") (pintype "passive"))
      (node (ref "R33") (pin "1") (pinfunction "1_1") (pintype "passive"))
      (node (ref "R53") (pin "1") (pinfunction "1_1") (pintype "passive"))
    )
    (net (code "70") (name "SHUNT_SUM_L") (class "Default")
      (node (ref "R16") (pin "1") (pinfunction "1_1") (pintype "passive"))
      (node (ref "R2") (pin "2") (pinfunction "2_2") (pintype "passive"))
      (node (ref "R33") (pin "3") (pinfunction "1_3") (pintype "passive"))
    )
    (net (code "71") (name "VREF") (class "Default")
      (node (ref "IC4") (pin "13") (pinfunction "-IN_13") (pintype "input"))
      (node (ref "IC4") (pin "14") (pinfunction "OUT_14") (pintype "output"))
      (node (ref "R12") (pin "6") (pinfunction "2_6") (pintype "passive"))
      (node (ref "R12") (pin "7") (pinfunction "2_7") (pintype "passive"))
      (node (ref "R13") (pin "6") (pinfunction "2_6") (pintype "passive"))
    )
    (net (code "72") (name "V_M1") (class "Default")
      (node (ref "C8") (pin "2") (pinfunction "2_2") (pintype "passive"))
      (node (ref "IC5") (pin "13") (pinfunction "O1_13") (pintype "bidirectional"))
      (node (ref "R11") (pin "8") (pinfunction "2_8") (pintype "passive"))
    )
    (net (code "73") (name "V_M2") (class "Default")
      (node (ref "C9") (pin "2") (pinfunction "2_2") (pintype "passive"))
      (node (ref "IC5") (pin "1") (pinfunction "O1_1") (pintype "bidirectional"))
      (node (ref "R11") (pin "7") (pinfunction "2_7") (pintype "passive"))
    )
    (net (code "74") (name "V_M3") (class "Default")
      (node (ref "C10") (pin "2") (pinfunction "2_2") (pintype "passive"))
      (node (ref "IC5") (pin "3") (pinfunction "O1_3") (pintype "bidirectional"))
      (node (ref "R11") (pin "6") (pinfunction "2_6") (pintype "passive"))
    )
    (net (code "75") (name "unconnected-(CON2-PadA1)") (class "Default")
      (node (ref "CON2") (pin "A1") (pinfunction "A1_A1") (pintype "passive"))
    )
    (net (code "76") (name "unconnected-(CON2-PadA3)") (class "Default")
      (node (ref "CON2") (pin "A3") (pinfunction "A3_A3") (pintype "passive"))
    )
    (net (code "77") (name "unconnected-(CON2-PadA4)") (class "Default")
      (node (ref "CON2") (pin "A4") (pinfunction "A4_A4") (pintype "passive"))
    )
    (net (code "78") (name "unconnected-(CON2-PadA5)") (class "Default")
      (node (ref "CON2") (pin "A5") (pinfunction "A5_A5") (pintype "passive"))
    )
    (net (code "79") (name "unconnected-(CON2-PadA8)") (class "Default")
      (node (ref "CON2") (pin "A8") (pinfunction "A8_A8") (pintype "passive"))
    )
    (net (code "80") (name "unconnected-(CON2-PadA9)") (class "Default")
      (node (ref "CON2") (pin "A9") (pinfunction "A9_A9") (pintype "passive"))
    )
    (net (code "81") (name "unconnected-(CON2-PadA10)") (class "Default")
      (node (ref "CON2") (pin "A10") (pinfunction "A10_A10") (pintype "passive"))
    )
    (net (code "82") (name "unconnected-(CON2-PadA11)") (class "Default")
      (node (ref "CON2") (pin "A11") (pinfunction "A11_A11") (pintype "passive"))
    )
    (net (code "83") (name "unconnected-(CON2-PadA12)") (class "Default")
      (node (ref "CON2") (pin "A12") (pinfunction "A12_A12") (pintype "passive"))
    )
    (net (code "84") (name "unconnected-(CON2-PadA13)") (class "Default")
      (node (ref "CON2") (pin "A13") (pinfunction "A13_A13") (pintype "passive"))
    )
    (net (code "85") (name "unconnected-(CON2-PadA18)") (class "Default")
      (node (ref "CON2") (pin "A18") (pinfunction "A18_A18") (pintype "passive"))
    )
    (net (code "86") (name "unconnected-(CON2-PadA19)") (class "Default")
      (node (ref "CON2") (pin "A19") (pinfunction "A19_A19") (pintype "passive"))
    )
    (net (code "87") (name "unconnected-(CON2-PadA20)") (class "Default")
      (node (ref "CON2") (pin "A20") (pinfunction "A20_A20") (pintype "passive"))
    )
    (net (code "88") (name "unconnected-(CON2B-A1-PadB1)") (class "Default")
      (node (ref "CON2") (pin "B1") (pinfunction "A1_B1") (pintype "passive"))
    )
    (net (code "89") (name "unconnected-(CON2B-A3-PadB3)") (class "Default")
      (node (ref "CON2") (pin "B3") (pinfunction "A3_B3") (pintype "passive"))
    )
    (net (code "90") (name "unconnected-(CON2B-A4-PadB4)") (class "Default")
      (node (ref "CON2") (pin "B4") (pinfunction "A4_B4") (pintype "passive"))
    )
    (net (code "91") (name "unconnected-(CON2B-A5-PadB5)") (class "Default")
      (node (ref "CON2") (pin "B5") (pinfunction "A5_B5") (pintype "passive"))
    )
    (net (code "92") (name "unconnected-(CON2B-A8-PadB8)") (class "Default")
      (node (ref "CON2") (pin "B8") (pinfunction "A8_B8") (pintype "passive"))
    )
    (net (code "93") (name "unconnected-(CON2B-A9-PadB9)") (class "Default")
      (node (ref "CON2") (pin "B9") (pinfunction "A9_B9") (pintype "passive"))
    )
    (net (code "94") (name "unconnected-(CON2B-A10-PadB10)") (class "Default")
      (node (ref "CON2") (pin "B10") (pinfunction "A10_B10") (pintype "passive"))
    )
    (net (code "95") (name "unconnected-(CON2B-A11-PadB11)") (class "Default")
      (node (ref "CON2") (pin "B11") (pinfunction "A11_B11") (pintype "passive"))
    )
    (net (code "96") (name "unconnected-(CON2B-A12-PadB12)") (class "Default")
      (node (ref "CON2") (pin "B12") (pinfunction "A12_B12") (pintype "passive"))
    )
    (net (code "97") (name "unconnected-(CON2B-A13-PadB13)") (class "Default")
      (node (ref "CON2") (pin "B13") (pinfunction "A13_B13") (pintype "passive"))
    )
    (net (code "98") (name "unconnected-(CON2B-A18-PadB18)") (class "Default")
      (node (ref "CON2") (pin "B18") (pinfunction "A18_B18") (pintype "passive"))
    )
    (net (code "99") (name "unconnected-(CON2B-A19-PadB19)") (class "Default")
      (node (ref "CON2") (pin "B19") (pinfunction "A19_B19") (pintype "passive"))
    )
    (net (code "100") (name "unconnected-(CON2B-A20-PadB20)") (class "Default")
      (node (ref "CON2") (pin "B20") (pinfunction "A20_B20") (pintype "passive"))
    )
    (net (code "101") (name "unconnected-(IC2C-O-Pad8)") (class "Default")
      (node (ref "IC2") (pin "8") (pinfunction "O_8") (pintype "output"))
    )
    (net (code "102") (name "unconnected-(IC2D-O-Pad11)") (class "Default")
      (node (ref "IC2") (pin "11") (pinfunction "O_11") (pintype "output"))
    )
    (net (code "103") (name "unconnected-(R4B-1-Pad2)") (class "Default")
      (node (ref "R4") (pin "2") (pinfunction "1_2") (pintype "passive"))
    )
    (net (code "104") (name "unconnected-(R4B-2-Pad7)") (class "Default")
      (node (ref "R4") (pin "7") (pinfunction "2_7") (pintype "passive"))
    )
  )
)
